# mcu.net
KiCad netlist of a schematic drawn in Altium Designer
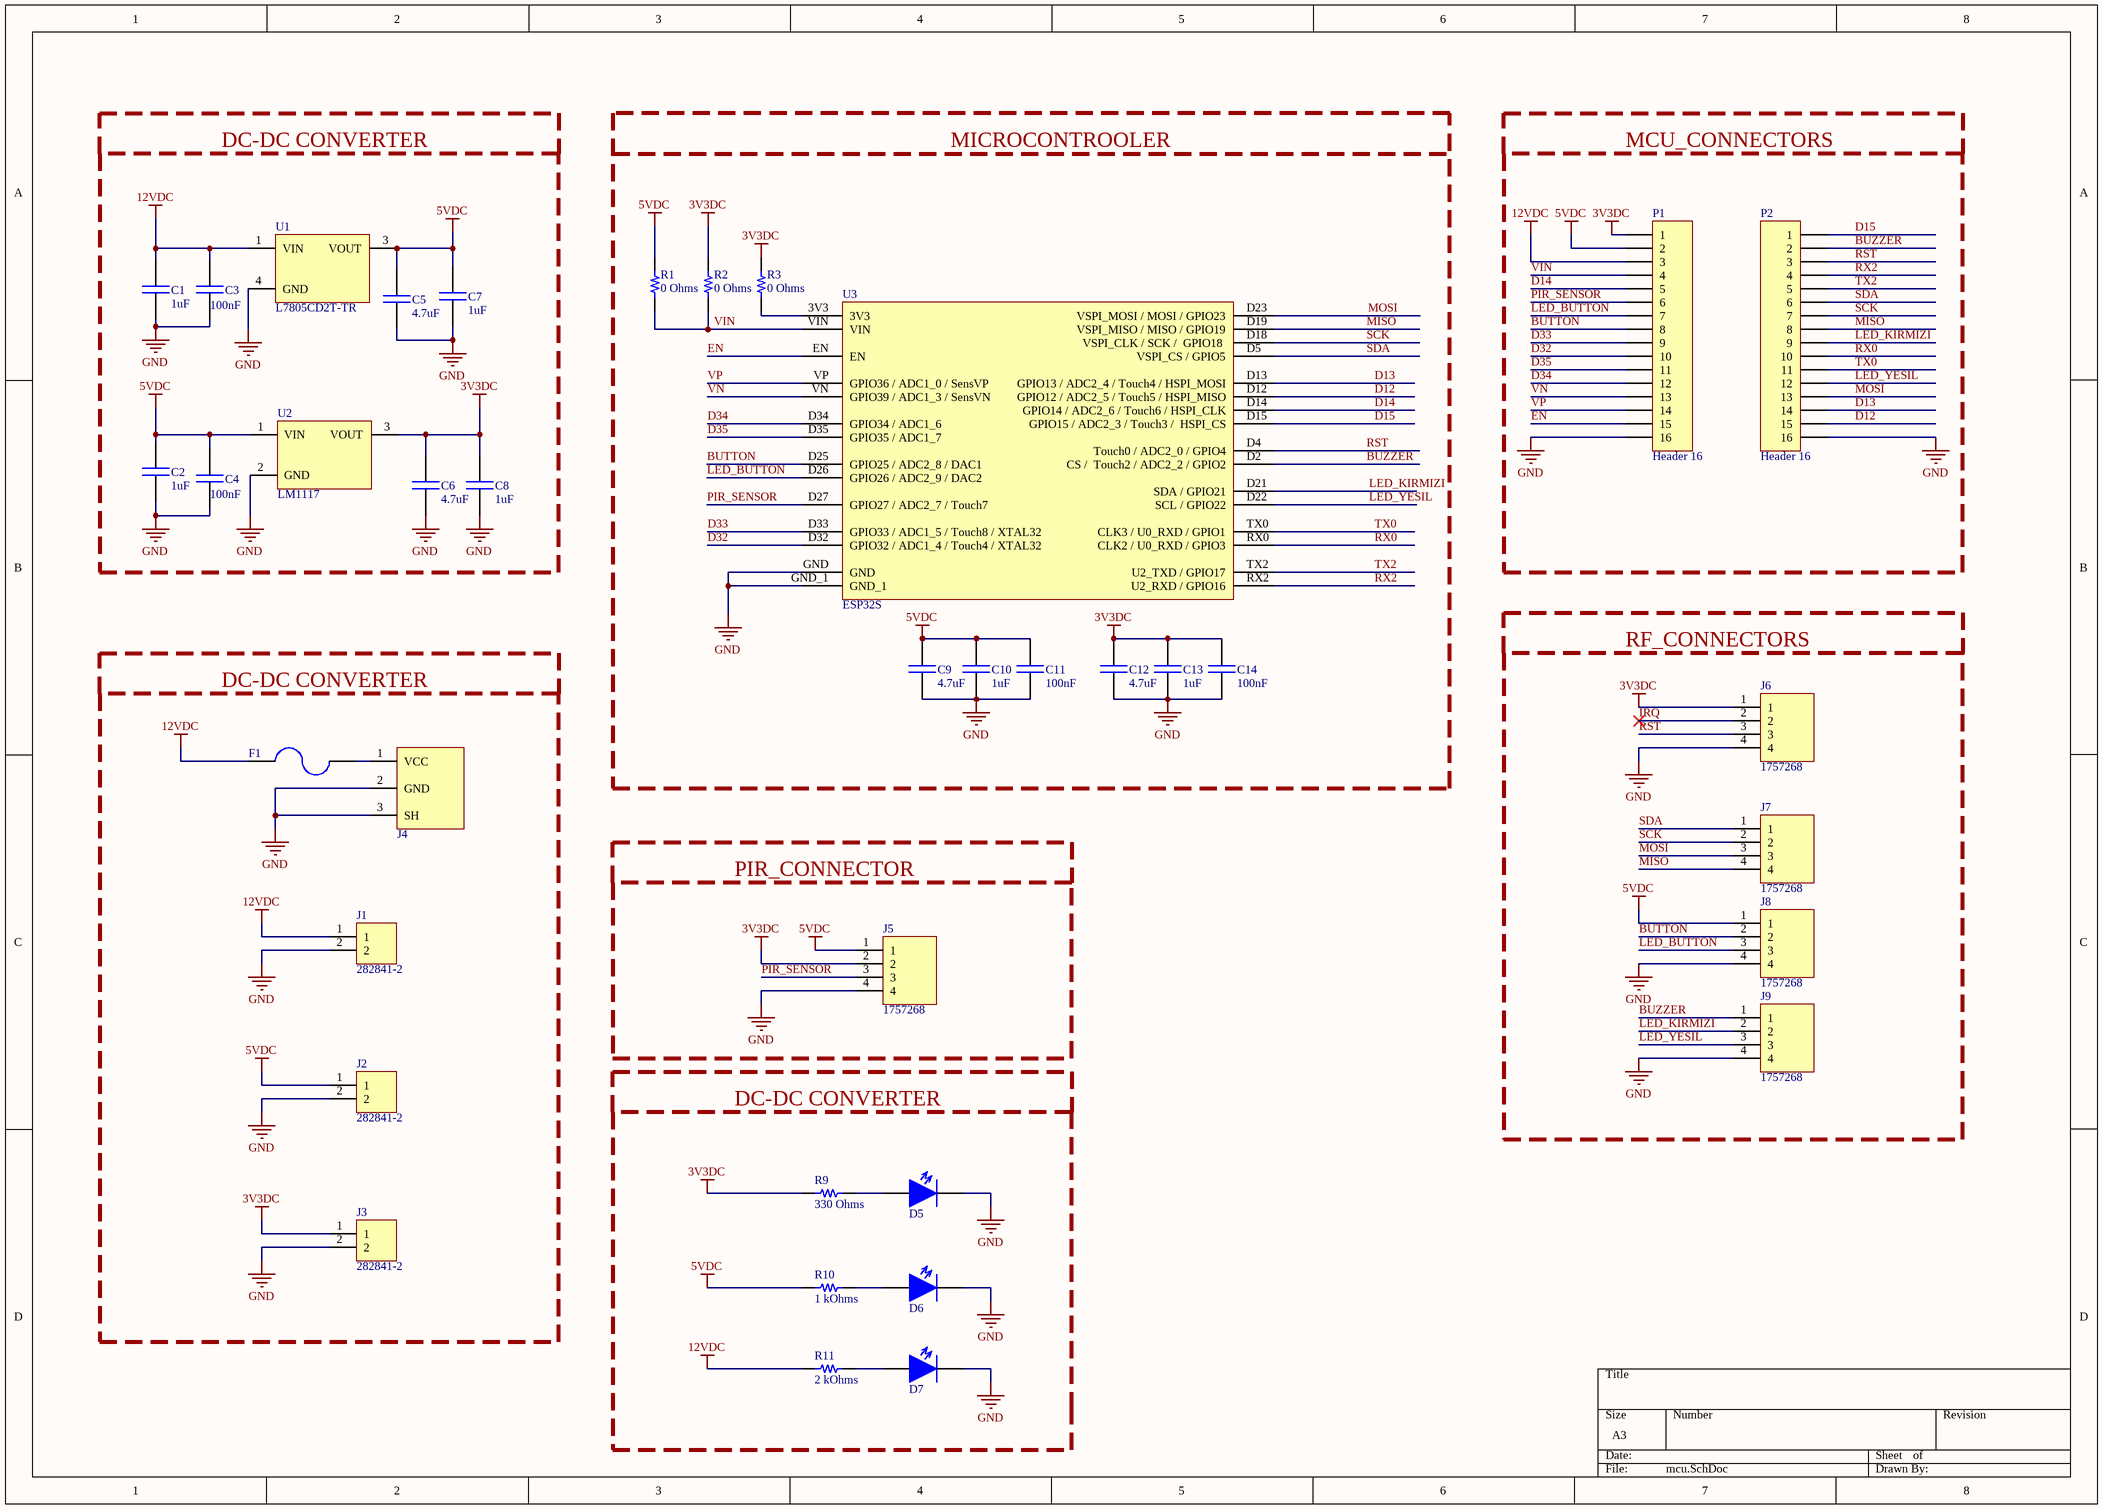
[diagram p0: mcu.SchDoc]

(export (version "E")
  (design (tool "Eeschema 10.0.6"))
  (components
    (comp (ref "C1")
      (value "CL21B105KBFNNNE")
      (footprint "CAP_0805")
      (description "CAP CER 1uF  %10 0805")
      (fields
        (field (name "MANUFACTURER") "Samsung")
        (field (name "TOLERANCE") "10%")
        (field (name "CAPACITANCE") "1uF")
        (field (name "DESIGNED BY") "EMRE")
      )
      (libsource (lib "Udemy_library_Integrated_Library1") (part "CAP CER 1uF 0805"))
    )
    (comp (ref "C2")
      (value "CL21B105KBFNNNE")
      (footprint "CAP_0805")
      (description "CAP CER 1uF  %10 0805")
      (fields
        (field (name "MANUFACTURER") "Samsung")
        (field (name "TOLERANCE") "10%")
        (field (name "CAPACITANCE") "1uF")
        (field (name "DESIGNED BY") "EMRE")
      )
      (libsource (lib "Udemy_library_Integrated_Library1") (part "CAP CER 1uF 0805"))
    )
    (comp (ref "C3")
      (value "CL21B104KBCNNNC")
      (footprint "CAP_0805")
      (description "CAP CER 100nF  %10 0805")
      (fields
        (field (name "MANUFACTURER") "Samsung")
        (field (name "TOLERANCE") "10%")
        (field (name "CAPACITANCE") "100nF")
        (field (name "DESIGNED BY") "EMRE")
      )
      (libsource (lib "Udemy_library_Integrated_Library1") (part "CAP CER 100nF 0805"))
    )
    (comp (ref "C4")
      (value "CL21B104KBCNNNC")
      (footprint "CAP_0805")
      (description "CAP CER 100nF  %10 0805")
      (fields
        (field (name "MANUFACTURER") "Samsung")
        (field (name "TOLERANCE") "10%")
        (field (name "CAPACITANCE") "100nF")
        (field (name "DESIGNED BY") "EMRE")
      )
      (libsource (lib "Udemy_library_Integrated_Library1") (part "CAP CER 100nF 0805"))
    )
    (comp (ref "C5")
      (value "CL21A475KAQNNNE")
      (footprint "CAP_0805")
      (description "CAP CER 4.7UF  %10 0805")
      (fields
        (field (name "MANUFACTURER") "Samsung")
        (field (name "TOLERANCE") "10%")
        (field (name "CAPACITANCE") "4.7uF")
        (field (name "DESIGNED BY") "EMRE")
      )
      (libsource (lib "Udemy_library_Integrated_Library1") (part "CAP CER 4.7uF 0805"))
    )
    (comp (ref "C6")
      (value "CL21A475KAQNNNE")
      (footprint "CAP_0805")
      (description "CAP CER 4.7UF  %10 0805")
      (fields
        (field (name "MANUFACTURER") "Samsung")
        (field (name "TOLERANCE") "10%")
        (field (name "CAPACITANCE") "4.7uF")
        (field (name "DESIGNED BY") "EMRE")
      )
      (libsource (lib "Udemy_library_Integrated_Library1") (part "CAP CER 4.7uF 0805"))
    )
    (comp (ref "C7")
      (value "CL21B105KBFNNNE")
      (footprint "CAP_0805")
      (description "CAP CER 1uF  %10 0805")
      (fields
        (field (name "MANUFACTURER") "Samsung")
        (field (name "TOLERANCE") "10%")
        (field (name "CAPACITANCE") "1uF")
        (field (name "DESIGNED BY") "EMRE")
      )
      (libsource (lib "Udemy_library_Integrated_Library1") (part "CAP CER 1uF 0805"))
    )
    (comp (ref "C8")
      (value "CL21B105KBFNNNE")
      (footprint "CAP_0805")
      (description "CAP CER 1uF  %10 0805")
      (fields
        (field (name "MANUFACTURER") "Samsung")
        (field (name "TOLERANCE") "10%")
        (field (name "CAPACITANCE") "1uF")
        (field (name "DESIGNED BY") "EMRE")
      )
      (libsource (lib "Udemy_library_Integrated_Library1") (part "CAP CER 1uF 0805"))
    )
    (comp (ref "C9")
      (value "CL21A475KAQNNNE")
      (footprint "CAP_0805")
      (description "CAP CER 4.7UF  %10 0805")
      (fields
        (field (name "MANUFACTURER") "Samsung")
        (field (name "TOLERANCE") "10%")
        (field (name "CAPACITANCE") "4.7uF")
        (field (name "DESIGNED BY") "EMRE")
      )
      (libsource (lib "Udemy_library_Integrated_Library1") (part "CAP CER 4.7uF 0805"))
    )
    (comp (ref "C10")
      (value "CL21B105KBFNNNE")
      (footprint "CAP_0805")
      (description "CAP CER 1uF  %10 0805")
      (fields
        (field (name "MANUFACTURER") "Samsung")
        (field (name "TOLERANCE") "10%")
        (field (name "CAPACITANCE") "1uF")
        (field (name "DESIGNED BY") "EMRE")
      )
      (libsource (lib "Udemy_library_Integrated_Library1") (part "CAP CER 1uF 0805"))
    )
    (comp (ref "C11")
      (value "CL21B104KBCNNNC")
      (footprint "CAP_0805")
      (description "CAP CER 100nF  %10 0805")
      (fields
        (field (name "MANUFACTURER") "Samsung")
        (field (name "TOLERANCE") "10%")
        (field (name "CAPACITANCE") "100nF")
        (field (name "DESIGNED BY") "EMRE")
      )
      (libsource (lib "Udemy_library_Integrated_Library1") (part "CAP CER 100nF 0805"))
    )
    (comp (ref "C12")
      (value "CL21A475KAQNNNE")
      (footprint "CAP_0805")
      (description "CAP CER 4.7UF  %10 0805")
      (fields
        (field (name "MANUFACTURER") "Samsung")
        (field (name "TOLERANCE") "10%")
        (field (name "CAPACITANCE") "4.7uF")
        (field (name "DESIGNED BY") "EMRE")
      )
      (libsource (lib "Udemy_library_Integrated_Library1") (part "CAP CER 4.7uF 0805"))
    )
    (comp (ref "C13")
      (value "CL21B105KBFNNNE")
      (footprint "CAP_0805")
      (description "CAP CER 1uF  %10 0805")
      (fields
        (field (name "MANUFACTURER") "Samsung")
        (field (name "TOLERANCE") "10%")
        (field (name "CAPACITANCE") "1uF")
        (field (name "DESIGNED BY") "EMRE")
      )
      (libsource (lib "Udemy_library_Integrated_Library1") (part "CAP CER 1uF 0805"))
    )
    (comp (ref "C14")
      (value "CL21B104KBCNNNC")
      (footprint "CAP_0805")
      (description "CAP CER 100nF  %10 0805")
      (fields
        (field (name "MANUFACTURER") "Samsung")
        (field (name "TOLERANCE") "10%")
        (field (name "CAPACITANCE") "100nF")
        (field (name "DESIGNED BY") "EMRE")
      )
      (libsource (lib "Udemy_library_Integrated_Library1") (part "CAP CER 100nF 0805"))
    )
    (comp (ref "D5")
      (value "LTST-C171GKT")
      (footprint "LED_GREEN_0805")
      (description "Green 569nm LED Indication - Discrete 2.1V 0805 (2012 Metric)")
      (fields (field (name "MANUFACTURER") "Vishay Lite-On") (field (name "DESIGNED BY") "EMRE"))
      (libsource (lib "Udemy_library_Integrated_Library1") (part "LED GREEN 0805"))
    )
    (comp (ref "D6")
      (value "LH R974-LP-1-0-20-R18")
      (footprint "LED_RED_0805")
      (description "Chipled 0805 Hyp Red 645NM")
      (fields
        (field (name "MANUFACTURER") "Osram Opto")
        (field (name "MANUFACTURER PART NUMBER") "LHR974-LP-1-0-20-R18")
        (field (name "DESIGNED BY") "EMRE")
      )
      (libsource (lib "Udemy_library_Integrated_Library1") (part "LED RED 0805"))
    )
    (comp (ref "D7")
      (value "LH R974-LP-1-0-20-R18")
      (footprint "LED_RED_0805")
      (description "Chipled 0805 Hyp Red 645NM")
      (fields
        (field (name "MANUFACTURER") "Osram Opto")
        (field (name "MANUFACTURER PART NUMBER") "LHR974-LP-1-0-20-R18")
        (field (name "DESIGNED BY") "EMRE")
      )
      (libsource (lib "Udemy_library_Integrated_Library1") (part "LED RED 0805"))
    )
    (comp (ref "F1")
      (value "FUSE 3413.0216.22")
      (footprint "FUSE 3413.0216.22")
      (description "Fuse Chip Fast Acting 1A 32V SMD Solder Pad 1206 Glass T/R VDE/cULus")
      (fields
        (field (name "MANUFACTURER") "Schurter")
        (field (name "MANUFACTURER PART NUMBER") "3413.0216.22")
        (field (name "DESIGNED BY") "EMRE")
      )
      (libsource (lib "Udemy_library_Integrated_Library1") (part "FUSE 3413.0216.22"))
    )
    (comp (ref "J1")
      (value "282841-2")
      (footprint "connector_2pİN")
      (description "Conn Terminal Block 2 POS 5.08mm Solder ST Thru-Hole 17.5A/Contact")
      (fields (field (name "MANUFACTURER") "TE Connectivity") (field (name "VOLTAGE") "300V"))
      (libsource (lib "Udemy_library_Integrated_Library1") (part "CONNECTOR_2Pin"))
    )
    (comp (ref "J2")
      (value "282841-2")
      (footprint "connector_2pİN")
      (description "Conn Terminal Block 2 POS 5.08mm Solder ST Thru-Hole 17.5A/Contact")
      (fields (field (name "MANUFACTURER") "TE Connectivity") (field (name "VOLTAGE") "300V"))
      (libsource (lib "Udemy_library_Integrated_Library1") (part "CONNECTOR_2Pin"))
    )
    (comp (ref "J3")
      (value "282841-2")
      (footprint "connector_2pİN")
      (description "Conn Terminal Block 2 POS 5.08mm Solder ST Thru-Hole 17.5A/Contact")
      (fields (field (name "MANUFACTURER") "TE Connectivity") (field (name "VOLTAGE") "300V"))
      (libsource (lib "Udemy_library_Integrated_Library1") (part "CONNECTOR_2Pin"))
    )
    (comp (ref "J4")
      (value "PJ-037AH-SMT-TR")
      (footprint "JACK")
      (description "2.0 x 6.3 mm, 5.0 A, Horizontal, Surface Mount (SMT), Dc Power Jack Connector")
      (fields (field (name "MANUFACTURER") "CUI") (field (name "DESIGNED BY") "EMRE"))
      (libsource (lib "Udemy_library_Integrated_Library1") (part "PJ-037AH-SMT-TR"))
    )
    (comp (ref "J5")
      (value "1757268")
      (footprint "CONNECTOR_4Pin")
      (description "Terminal Header; 12 A; 5.08 mm; 4; Solder Mount; 1.4 mm; 4 kV; 250 V; PBT")
      (fields (field (name "MANUFACTURER") "Phoenix Contact") (field (name "VOLTAGE") "300V"))
      (libsource (lib "Udemy_library_Integrated_Library1") (part "CONNECTOR_4Pin"))
    )
    (comp (ref "J6")
      (value "1757268")
      (footprint "CONNECTOR_4Pin")
      (description "Terminal Header; 12 A; 5.08 mm; 4; Solder Mount; 1.4 mm; 4 kV; 250 V; PBT")
      (fields (field (name "MANUFACTURER") "Phoenix Contact") (field (name "VOLTAGE") "300V"))
      (libsource (lib "Udemy_library_Integrated_Library1") (part "CONNECTOR_4Pin"))
    )
    (comp (ref "J7")
      (value "1757268")
      (footprint "CONNECTOR_4Pin")
      (description "Terminal Header; 12 A; 5.08 mm; 4; Solder Mount; 1.4 mm; 4 kV; 250 V; PBT")
      (fields (field (name "MANUFACTURER") "Phoenix Contact") (field (name "VOLTAGE") "300V"))
      (libsource (lib "Udemy_library_Integrated_Library1") (part "CONNECTOR_4Pin"))
    )
    (comp (ref "J8")
      (value "1757268")
      (footprint "CONNECTOR_4Pin")
      (description "Terminal Header; 12 A; 5.08 mm; 4; Solder Mount; 1.4 mm; 4 kV; 250 V; PBT")
      (fields (field (name "MANUFACTURER") "Phoenix Contact") (field (name "VOLTAGE") "300V"))
      (libsource (lib "Udemy_library_Integrated_Library1") (part "CONNECTOR_4Pin"))
    )
    (comp (ref "J9")
      (value "1757268")
      (footprint "CONNECTOR_4Pin")
      (description "Terminal Header; 12 A; 5.08 mm; 4; Solder Mount; 1.4 mm; 4 kV; 250 V; PBT")
      (fields (field (name "MANUFACTURER") "Phoenix Contact") (field (name "VOLTAGE") "300V"))
      (libsource (lib "Udemy_library_Integrated_Library1") (part "CONNECTOR_4Pin"))
    )
    (comp (ref "P1")
      (value "Header 16")
      (footprint "HDR1X16")
      (description "Header, 16-Pin")
      (fields (field (name "PUBLISHER") "Altium Limited"))
      (libsource (lib "Miscellaneous Connectors") (part "Header 16"))
    )
    (comp (ref "P2")
      (value "Header 16")
      (footprint "HDR1X16")
      (description "Header, 16-Pin")
      (fields (field (name "PUBLISHER") "Altium Limited"))
      (libsource (lib "") (part "Header 16_1"))
    )
    (comp (ref "R1")
      (value "0 Ohms")
      (footprint "RES 1206_3216")
      (description "RES 0 OHM JUMPER 1206")
      (fields (field (name "PART NUMBER") "RC1206FR-130RL") (field (name "MANUFACTURER") "Yageo"))
      (libsource (lib "Celestial Altium Library - altium_library") (part "Resistor"))
    )
    (comp (ref "R2")
      (value "0 Ohms")
      (footprint "RES 1206_3216")
      (description "RES 0 OHM JUMPER 1206")
      (fields (field (name "PART NUMBER") "RC1206FR-130RL") (field (name "MANUFACTURER") "Yageo"))
      (libsource (lib "Celestial Altium Library - altium_library") (part "Resistor"))
    )
    (comp (ref "R3")
      (value "0 Ohms")
      (footprint "RES 1206_3216")
      (description "RES 0 OHM JUMPER 1206")
      (fields (field (name "PART NUMBER") "RC1206FR-130RL") (field (name "MANUFACTURER") "Yageo"))
      (libsource (lib "Celestial Altium Library - altium_library") (part "Resistor"))
    )
    (comp (ref "R9")
      (value "330 Ohms")
      (footprint "RES 0805_2012")
      (description "RES SMD 330 OHM 5% 0.4W 0805")
      (fields (field (name "PART NUMBER") "ESR10EZPJ331") (field (name "MANUFACTURER") "Rohm Semiconductor"))
      (libsource (lib "Celestial Altium Library - altium_library") (part "Resistor"))
    )
    (comp (ref "R10")
      (value "1 kOhms")
      (footprint "RES 0805_2012")
      (description "RES 1K OHM 0.1% 1/8W 0805")
      (fields
        (field (name "PART NUMBER") "ERA-6AEB102V")
        (field (name "MANUFACTURER") "Panasonic Electronic Components")
      )
      (libsource (lib "Celestial Altium Library - altium_library") (part "Resistor"))
    )
    (comp (ref "R11")
      (value "2 kOhms")
      (footprint "RES 0805_2012")
      (description "RES SMD 2K OHM 1% 1/8W 0805")
      (fields (field (name "PART NUMBER") "RC0805FR-072KP") (field (name "MANUFACTURER") "Yageo"))
      (libsource (lib "Celestial Altium Library - altium_library") (part "Resistor"))
    )
    (comp (ref "U1")
      (value "L7805CD2T-TR")
      (footprint "D2PAK")
      (libsource (lib "Udemy_library_Integrated_Library1") (part "7805"))
    )
    (comp (ref "U2")
      (value "LM1117")
      (footprint "SOT223")
      (libsource (lib "Udemy_library_Integrated_Library1") (part "LM1117"))
    )
    (comp (ref "U3")
      (value "ESP32S")
      (footprint "ESP32_BOARD")
      (libsource (lib "Udemy_library_Integrated_Library1") (part "ESP32_BOARD"))
    )
  )
  (nets
    (net (code "1") (name "/BUTTON") (class "Default")
      (node (ref "J8") (pin "2") (pinfunction "2_2") (pintype "passive"))
      (node (ref "P1") (pin "8") (pinfunction "8_8") (pintype "passive"))
      (node (ref "U3") (pin "D25") (pinfunction "GPIO25_/_ADC2_8_/_DAC1_D25") (pintype "passive"))
    )
    (net (code "2") (name "/BUZZER") (class "Default")
      (node (ref "J9") (pin "1") (pinfunction "1_1") (pintype "passive"))
      (node (ref "P2") (pin "2") (pinfunction "2_2") (pintype "passive"))
      (node (ref "U3") (pin "D2") (pinfunction "CS_/__Touch2_/_ADC2_2_/_GPIO2_D2") (pintype "passive"))
    )
    (net (code "3") (name "/D12") (class "Default")
      (node (ref "P2") (pin "15") (pinfunction "15_15") (pintype "passive"))
      (node (ref "U3") (pin "D12") (pinfunction "GPIO12_/_ADC2_5_/_Touch5_/_HSPI_MISO_D12") (pintype "passive"))
    )
    (net (code "4") (name "/D13") (class "Default")
      (node (ref "P2") (pin "14") (pinfunction "14_14") (pintype "passive"))
      (node (ref "U3") (pin "D13") (pinfunction "GPIO13_/_ADC2_4_/_Touch4_/_HSPI_MOSI_D13") (pintype "passive"))
    )
    (net (code "5") (name "/D14") (class "Default")
      (node (ref "P1") (pin "5") (pinfunction "5_5") (pintype "passive"))
      (node (ref "U3") (pin "D14") (pinfunction "GPIO14_/_ADC2_6_/_Touch6_/_HSPI_CLK_D14") (pintype "passive"))
    )
    (net (code "6") (name "/D15") (class "Default")
      (node (ref "P2") (pin "1") (pinfunction "1_1") (pintype "passive"))
      (node (ref "U3") (pin "D15") (pinfunction "GPIO15_/_ADC2_3_/_Touch3_/__HSPI_CS_D15") (pintype "passive"))
    )
    (net (code "7") (name "/D32") (class "Default")
      (node (ref "P1") (pin "10") (pinfunction "10_10") (pintype "passive"))
      (node (ref "U3") (pin "D32") (pinfunction "GPIO32_/_ADC1_4_/_Touch4_/_XTAL32_D32") (pintype "passive"))
    )
    (net (code "8") (name "/D33") (class "Default")
      (node (ref "P1") (pin "9") (pinfunction "9_9") (pintype "passive"))
      (node (ref "U3") (pin "D33") (pinfunction "GPIO33_/_ADC1_5_/_Touch8_/_XTAL32_D33") (pintype "passive"))
    )
    (net (code "9") (name "/D34") (class "Default")
      (node (ref "P1") (pin "12") (pinfunction "12_12") (pintype "passive"))
      (node (ref "U3") (pin "D34") (pinfunction "GPIO34_/_ADC1_6_D34") (pintype "passive"))
    )
    (net (code "10") (name "/D35") (class "Default")
      (node (ref "P1") (pin "11") (pinfunction "11_11") (pintype "passive"))
      (node (ref "U3") (pin "D35") (pinfunction "GPIO35_/_ADC1_7_D35") (pintype "passive"))
    )
    (net (code "11") (name "/EN") (class "Default")
      (node (ref "P1") (pin "15") (pinfunction "15_15") (pintype "passive"))
      (node (ref "U3") (pin "EN") (pinfunction "EN_EN") (pintype "passive"))
    )
    (net (code "12") (name "/IRQ") (class "Default")
      (node (ref "J6") (pin "2") (pinfunction "2_2") (pintype "passive+no_connect"))
    )
    (net (code "13") (name "/LED_BUTTON") (class "Default")
      (node (ref "J8") (pin "3") (pinfunction "3_3") (pintype "passive"))
      (node (ref "P1") (pin "7") (pinfunction "7_7") (pintype "passive"))
      (node (ref "U3") (pin "D26") (pinfunction "GPIO26_/_ADC2_9_/_DAC2_D26") (pintype "passive"))
    )
    (net (code "14") (name "/LED_KIRMIZI") (class "Default")
      (node (ref "J9") (pin "2") (pinfunction "2_2") (pintype "passive"))
      (node (ref "P2") (pin "9") (pinfunction "9_9") (pintype "passive"))
      (node (ref "U3") (pin "D21") (pinfunction "SDA_/_GPIO21_D21") (pintype "passive"))
    )
    (net (code "15") (name "/LED_YESIL") (class "Default")
      (node (ref "J9") (pin "3") (pinfunction "3_3") (pintype "passive"))
      (node (ref "P2") (pin "12") (pinfunction "12_12") (pintype "passive"))
      (node (ref "U3") (pin "D22") (pinfunction "SCL_/_GPIO22_D22") (pintype "passive"))
    )
    (net (code "16") (name "/MISO") (class "Default")
      (node (ref "J7") (pin "4") (pinfunction "4_4") (pintype "passive"))
      (node (ref "P2") (pin "8") (pinfunction "8_8") (pintype "passive"))
      (node (ref "U3") (pin "D19") (pinfunction "_VSPI_MISO_/_MISO_/_GPIO19_D19") (pintype "passive"))
    )
    (net (code "17") (name "/MOSI") (class "Default")
      (node (ref "J7") (pin "3") (pinfunction "3_3") (pintype "passive"))
      (node (ref "P2") (pin "13") (pinfunction "13_13") (pintype "passive"))
      (node (ref "U3") (pin "D23") (pinfunction "VSPI_MOSI_/_MOSI_/_GPIO23_D23") (pintype "passive"))
    )
    (net (code "18") (name "/PIR_SENSOR") (class "Default")
      (node (ref "J5") (pin "3") (pinfunction "3_3") (pintype "passive"))
      (node (ref "P1") (pin "6") (pinfunction "6_6") (pintype "passive"))
      (node (ref "U3") (pin "D27") (pinfunction "GPIO27_/_ADC2_7_/_Touch7_D27") (pintype "passive"))
    )
    (net (code "19") (name "/RST") (class "Default")
      (node (ref "J6") (pin "3") (pinfunction "3_3") (pintype "passive"))
      (node (ref "P2") (pin "3") (pinfunction "3_3") (pintype "passive"))
      (node (ref "U3") (pin "D4") (pinfunction "Touch0_/_ADC2_0_/_GPIO4_D4") (pintype "passive"))
    )
    (net (code "20") (name "/RX0") (class "Default")
      (node (ref "P2") (pin "10") (pinfunction "10_10") (pintype "passive"))
      (node (ref "U3") (pin "RX0") (pinfunction "CLK2_/_U0_RXD_/_GPIO3_RX0") (pintype "passive"))
    )
    (net (code "21") (name "/RX2") (class "Default")
      (node (ref "P2") (pin "4") (pinfunction "4_4") (pintype "passive"))
      (node (ref "U3") (pin "RX2") (pinfunction "U2_RXD_/_GPIO16_RX2") (pintype "passive"))
    )
    (net (code "22") (name "/SCK") (class "Default")
      (node (ref "J7") (pin "2") (pinfunction "2_2") (pintype "passive"))
      (node (ref "P2") (pin "7") (pinfunction "7_7") (pintype "passive"))
      (node (ref "U3") (pin "D18") (pinfunction "VSPI_CLK_/_SCK_/__GPIO18_D18") (pintype "passive"))
    )
    (net (code "23") (name "/SDA") (class "Default")
      (node (ref "J7") (pin "1") (pinfunction "1_1") (pintype "passive"))
      (node (ref "P2") (pin "6") (pinfunction "6_6") (pintype "passive"))
      (node (ref "U3") (pin "D5") (pinfunction "VSPI_CS_/_GPIO5_D5") (pintype "passive"))
    )
    (net (code "24") (name "/TX0") (class "Default")
      (node (ref "P2") (pin "11") (pinfunction "11_11") (pintype "passive"))
      (node (ref "U3") (pin "TX0") (pinfunction "CLK3_/_U0_RXD_/_GPIO1_TX0") (pintype "passive"))
    )
    (net (code "25") (name "/TX2") (class "Default")
      (node (ref "P2") (pin "5") (pinfunction "5_5") (pintype "passive"))
      (node (ref "U3") (pin "TX2") (pinfunction "U2_TXD_/_GPIO17_TX2") (pintype "passive"))
    )
    (net (code "26") (name "/VIN") (class "Default")
      (node (ref "P1") (pin "4") (pinfunction "4_4") (pintype "passive"))
      (node (ref "R1") (pin "1") (pinfunction "1_1") (pintype "passive"))
      (node (ref "R2") (pin "1") (pinfunction "1_1") (pintype "passive"))
      (node (ref "U3") (pin "VIN") (pinfunction "VIN_VIN") (pintype "passive"))
    )
    (net (code "27") (name "/VN") (class "Default")
      (node (ref "P1") (pin "13") (pinfunction "13_13") (pintype "passive"))
      (node (ref "U3") (pin "VN") (pinfunction "GPIO39_/_ADC1_3_/_SensVN_VN") (pintype "passive"))
    )
    (net (code "28") (name "/VP") (class "Default")
      (node (ref "P1") (pin "14") (pinfunction "14_14") (pintype "passive"))
      (node (ref "U3") (pin "VP") (pinfunction "GPIO36_/_ADC1_0_/_SensVP_VP") (pintype "passive"))
    )
    (net (code "29") (name "3V3DC") (class "Default")
      (node (ref "C12") (pin "2") (pinfunction "2_2") (pintype "passive"))
      (node (ref "C13") (pin "2") (pinfunction "2_2") (pintype "passive"))
      (node (ref "C14") (pin "2") (pinfunction "2_2") (pintype "passive"))
      (node (ref "C6") (pin "2") (pinfunction "2_2") (pintype "passive"))
      (node (ref "C8") (pin "2") (pinfunction "2_2") (pintype "passive"))
      (node (ref "J3") (pin "1") (pinfunction "1_1") (pintype "passive"))
      (node (ref "J5") (pin "2") (pinfunction "2_2") (pintype "passive"))
      (node (ref "J6") (pin "1") (pinfunction "1_1") (pintype "passive"))
      (node (ref "P1") (pin "1") (pinfunction "1_1") (pintype "passive"))
      (node (ref "R2") (pin "2") (pinfunction "2_2") (pintype "passive"))
      (node (ref "R3") (pin "2") (pinfunction "2_2") (pintype "passive"))
      (node (ref "R9") (pin "1") (pinfunction "1_1") (pintype "passive"))
      (node (ref "U2") (pin "3") (pinfunction "VOUT_3") (pintype "passive"))
    )
    (net (code "30") (name "5VDC") (class "Default")
      (node (ref "C10") (pin "2") (pinfunction "2_2") (pintype "passive"))
      (node (ref "C11") (pin "2") (pinfunction "2_2") (pintype "passive"))
      (node (ref "C2") (pin "2") (pinfunction "2_2") (pintype "passive"))
      (node (ref "C4") (pin "2") (pinfunction "2_2") (pintype "passive"))
      (node (ref "C5") (pin "2") (pinfunction "2_2") (pintype "passive"))
      (node (ref "C7") (pin "2") (pinfunction "2_2") (pintype "passive"))
      (node (ref "C9") (pin "2") (pinfunction "2_2") (pintype "passive"))
      (node (ref "J2") (pin "1") (pinfunction "1_1") (pintype "passive"))
      (node (ref "J5") (pin "1") (pinfunction "1_1") (pintype "passive"))
      (node (ref "J8") (pin "1") (pinfunction "1_1") (pintype "passive"))
      (node (ref "P1") (pin "2") (pinfunction "2_2") (pintype "passive"))
      (node (ref "R1") (pin "2") (pinfunction "2_2") (pintype "passive"))
      (node (ref "R10") (pin "1") (pinfunction "1_1") (pintype "passive"))
      (node (ref "U1") (pin "3") (pinfunction "VOUT_3") (pintype "passive"))
      (node (ref "U2") (pin "1") (pinfunction "VIN_1") (pintype "passive"))
    )
    (net (code "31") (name "12VDC") (class "Default")
      (node (ref "C1") (pin "2") (pinfunction "2_2") (pintype "passive"))
      (node (ref "C3") (pin "2") (pinfunction "2_2") (pintype "passive"))
      (node (ref "F1") (pin "1") (pinfunction "1_1") (pintype "passive"))
      (node (ref "J1") (pin "1") (pinfunction "1_1") (pintype "passive"))
      (node (ref "P1") (pin "3") (pinfunction "3_3") (pintype "passive"))
      (node (ref "R11") (pin "1") (pinfunction "1_1") (pintype "passive"))
      (node (ref "U1") (pin "1") (pinfunction "VIN_1") (pintype "passive"))
    )
    (net (code "32") (name "GND") (class "Default")
      (node (ref "C1") (pin "1") (pinfunction "1_1") (pintype "passive"))
      (node (ref "C10") (pin "1") (pinfunction "1_1") (pintype "passive"))
      (node (ref "C11") (pin "1") (pinfunction "1_1") (pintype "passive"))
      (node (ref "C12") (pin "1") (pinfunction "1_1") (pintype "passive"))
      (node (ref "C13") (pin "1") (pinfunction "1_1") (pintype "passive"))
      (node (ref "C14") (pin "1") (pinfunction "1_1") (pintype "passive"))
      (node (ref "C2") (pin "1") (pinfunction "1_1") (pintype "passive"))
      (node (ref "C3") (pin "1") (pinfunction "1_1") (pintype "passive"))
      (node (ref "C4") (pin "1") (pinfunction "1_1") (pintype "passive"))
      (node (ref "C5") (pin "1") (pinfunction "1_1") (pintype "passive"))
      (node (ref "C6") (pin "1") (pinfunction "1_1") (pintype "passive"))
      (node (ref "C7") (pin "1") (pinfunction "1_1") (pintype "passive"))
      (node (ref "C8") (pin "1") (pinfunction "1_1") (pintype "passive"))
      (node (ref "C9") (pin "1") (pinfunction "1_1") (pintype "passive"))
      (node (ref "D5") (pin "1") (pinfunction "1_1") (pintype "passive"))
      (node (ref "D6") (pin "1") (pinfunction "1_1") (pintype "passive"))
      (node (ref "D7") (pin "1") (pinfunction "1_1") (pintype "passive"))
      (node (ref "J1") (pin "2") (pinfunction "2_2") (pintype "passive"))
      (node (ref "J2") (pin "2") (pinfunction "2_2") (pintype "passive"))
      (node (ref "J3") (pin "2") (pinfunction "2_2") (pintype "passive"))
      (node (ref "J4") (pin "2") (pinfunction "GND_2") (pintype "power_in"))
      (node (ref "J4") (pin "3") (pinfunction "SH_3") (pintype "power_in"))
      (node (ref "J5") (pin "4") (pinfunction "4_4") (pintype "passive"))
      (node (ref "J6") (pin "4") (pinfunction "4_4") (pintype "passive"))
      (node (ref "J8") (pin "4") (pinfunction "4_4") (pintype "passive"))
      (node (ref "J9") (pin "4") (pinfunction "4_4") (pintype "passive"))
      (node (ref "P1") (pin "16") (pinfunction "16_16") (pintype "passive"))
      (node (ref "P2") (pin "16") (pinfunction "16_16") (pintype "passive"))
      (node (ref "U1") (pin "4") (pinfunction "GND_4") (pintype "passive"))
      (node (ref "U2") (pin "2") (pinfunction "GND_2") (pintype "passive"))
      (node (ref "U3") (pin "GND") (pinfunction "GND_GND") (pintype "passive"))
      (node (ref "U3") (pin "GND_1") (pinfunction "GND_1_GND_1") (pintype "passive"))
    )
    (net (code "33") (name "Net-(D5-Pad2)") (class "Default")
      (node (ref "D5") (pin "2") (pinfunction "2_2") (pintype "passive"))
      (node (ref "R9") (pin "2") (pinfunction "2_2") (pintype "passive"))
    )
    (net (code "34") (name "Net-(D6-Pad2)") (class "Default")
      (node (ref "D6") (pin "2") (pinfunction "2_2") (pintype "passive"))
      (node (ref "R10") (pin "2") (pinfunction "2_2") (pintype "passive"))
    )
    (net (code "35") (name "Net-(D7-Pad2)") (class "Default")
      (node (ref "D7") (pin "2") (pinfunction "2_2") (pintype "passive"))
      (node (ref "R11") (pin "2") (pinfunction "2_2") (pintype "passive"))
    )
    (net (code "36") (name "Net-(J4-VCC)") (class "Default")
      (node (ref "F1") (pin "2") (pinfunction "2_2") (pintype "passive"))
      (node (ref "J4") (pin "1") (pinfunction "VCC_1") (pintype "power_in"))
    )
    (net (code "37") (name "Net-(R3-Pad1)") (class "Default")
      (node (ref "R3") (pin "1") (pinfunction "1_1") (pintype "passive"))
      (node (ref "U3") (pin "3V3") (pinfunction "3V3_3V3") (pintype "passive"))
    )
  )
)
